# USB.net
KiCad netlist of a schematic drawn in Altium Designer
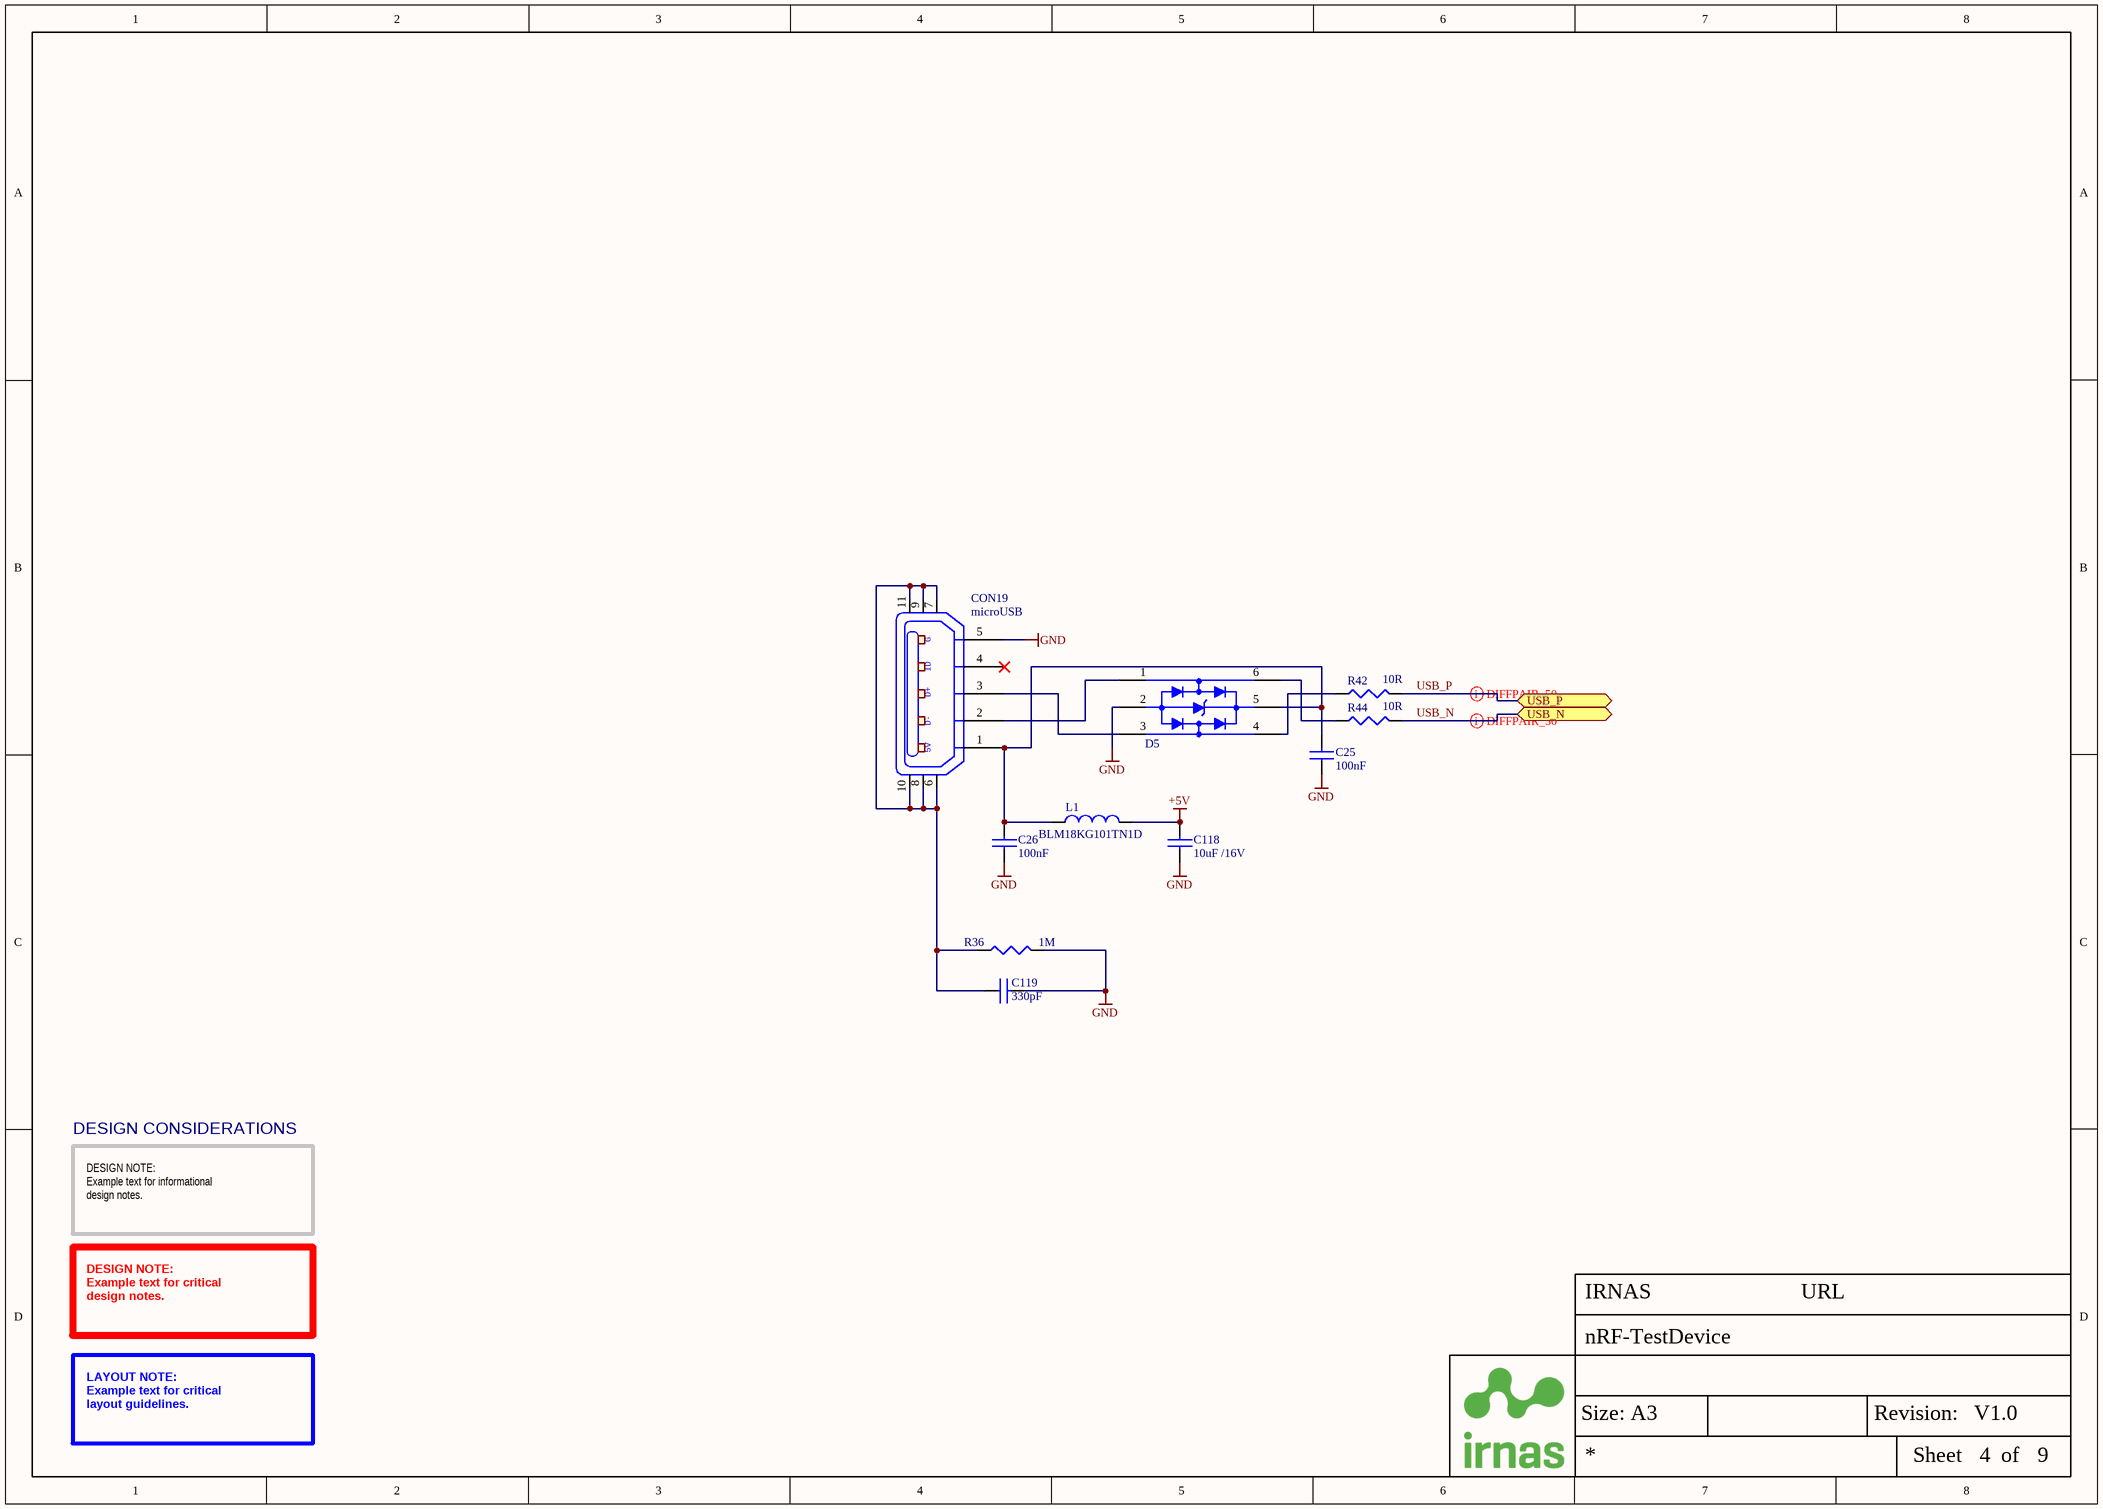
[diagram p0: USB.SchDoc]

(export (version "E")
  (design (tool "Eeschema 10.0.6"))
  (components
    (comp (ref "C25")
      (value "100nF")
      (footprint "CAP0402")
      (fields
        (field (name "MANUFACTURER") "Multicomp")
        (field (name "MANUFACTURER PART NUMBER") "MC0402X104J160CT")
        (field (name "TOLERANCE") "5%")
      )
      (libsource (lib "Passive") (part "C - 100nF/0402"))
    )
    (comp (ref "C26")
      (value "100nF")
      (footprint "CAP0402")
      (fields
        (field (name "MANUFACTURER") "Multicomp")
        (field (name "MANUFACTURER PART NUMBER") "MC0402X104J160CT")
        (field (name "TOLERANCE") "5%")
      )
      (libsource (lib "Passive") (part "C - 100nF/0402"))
    )
    (comp (ref "C118")
      (value "10uF /16V")
      (footprint "CAP0805")
      (description "TDK - CGA4J1X5R1C106K125AC - CAP, MLCC, X5R, 10UF, 16V, 0805")
      (fields
        (field (name "MANUFACTURER") "TDK")
        (field (name "MANUFACTURER PART NUMBER") "CGA4J1X5R1C106K125AC")
      )
      (libsource (lib "Passive") (part "C - 10uF /16V"))
    )
    (comp (ref "C119")
      (value "330pF")
      (footprint "CAP0603")
      (description "Cap Ceramic 330pF 50V C0G 5% SMD 0603 125C Paper T/R")
      (fields
        (field (name "MANUFACTURER") "Walsin Technologies")
        (field (name "MANUFACTURER PART NUMBER") "0603N331J500CT")
      )
      (libsource (lib "Passive") (part "C - 330pF"))
    )
    (comp (ref "CON19")
      (value "microUSB")
      (footprint "microUSB-CHINA")
      (libsource (lib "Connectors") (part "Micro USB CHINA 1"))
    )
    (comp (ref "D5")
      (value "USBLC6-2SC6")
      (footprint "SOT23-6")
      (description "ESD Protection Device, 17 V, SOT-23, 6 Pins, 6 V, 85 W, USBLC Series")
      (libsource (lib "Active") (part "D_ESD - USBLC6-2SC6"))
    )
    (comp (ref "L1")
      (value "BLM18KG101TN1D")
      (footprint "IND0603")
      (description "Ferrite Bead, 0603 [1608 Metric], 100 ohm, 3 A, BLM18K Series, 0.03 ohm, ± 25%")
      (libsource (lib "Passive") (part "L - BLM18KG101TN1D"))
    )
    (comp (ref "R36")
      (value "1M")
      (footprint "RES0603")
      (description "MULTICOMP - MC0063W060311M - RES, THICK FILM, 1M, 1%, 0.063W, 0603")
      (fields
        (field (name "MANUFACTURER") "MULTICOMP")
        (field (name "MANUFACTURER PART NUMBER") "MC0063W060311M")
      )
      (libsource (lib "Passive") (part "R - 1M"))
    )
    (comp (ref "R42")
      (value "10R")
      (footprint "RES0402")
      (description "SMD Chip Resistor, 0402 [1005 Metric], 10 ohm, CRCW e3 Series, 50 V, Thick Film, 63 mW")
      (fields
        (field (name "MANUFACTURER") "VISHAY")
        (field (name "MANUFACTURER PART NUMBER") "RCA060310R0FKEA")
      )
      (libsource (lib "Passive") (part "R - 10R/0402"))
    )
    (comp (ref "R44")
      (value "10R")
      (footprint "RES0402")
      (description "SMD Chip Resistor, 0402 [1005 Metric], 10 ohm, CRCW e3 Series, 50 V, Thick Film, 63 mW")
      (fields
        (field (name "MANUFACTURER") "VISHAY")
        (field (name "MANUFACTURER PART NUMBER") "RCA060310R0FKEA")
      )
      (libsource (lib "Passive") (part "R - 10R/0402"))
    )
  )
  (nets
    (net (code "1") (name "+5V") (class "Default")
      (node (ref "C118") (pin "2") (pinfunction "2_2") (pintype "passive"))
      (node (ref "L1") (pin "2") (pinfunction "2_2") (pintype "passive"))
    )
    (net (code "2") (name "/USB_N") (class "Default")
      (node (ref "R44") (pin "2") (pinfunction "2_2") (pintype "passive"))
    )
    (net (code "3") (name "/USB_P") (class "Default")
      (node (ref "R42") (pin "2") (pinfunction "2_2") (pintype "passive"))
    )
    (net (code "4") (name "GND") (class "Default")
      (node (ref "C118") (pin "1") (pinfunction "1_1") (pintype "passive"))
      (node (ref "C119") (pin "2") (pinfunction "2_2") (pintype "passive"))
      (node (ref "C25") (pin "1") (pinfunction "1_1") (pintype "passive"))
      (node (ref "C26") (pin "1") (pinfunction "1_1") (pintype "passive"))
      (node (ref "CON19") (pin "5") (pinfunction "P5_5") (pintype "passive"))
      (node (ref "D5") (pin "2") (pinfunction "2_2") (pintype "passive"))
      (node (ref "R36") (pin "2") (pinfunction "2_2") (pintype "passive"))
    )
    (net (code "5") (name "Net-(C119-Pad1)") (class "Default")
      (node (ref "C119") (pin "1") (pinfunction "1_1") (pintype "passive"))
      (node (ref "CON19") (pin "10") (pinfunction "10_10") (pintype "passive"))
      (node (ref "CON19") (pin "11") (pinfunction "11_11") (pintype "passive"))
      (node (ref "CON19") (pin "6") (pinfunction "6_6") (pintype "passive"))
      (node (ref "CON19") (pin "7") (pinfunction "7_7") (pintype "passive"))
      (node (ref "CON19") (pin "8") (pinfunction "8_8") (pintype "passive"))
      (node (ref "CON19") (pin "9") (pinfunction "9_9") (pintype "passive"))
      (node (ref "R36") (pin "1") (pinfunction "1_1") (pintype "passive"))
    )
    (net (code "6") (name "Net-(CON19-P1)") (class "Default")
      (node (ref "C25") (pin "2") (pinfunction "2_2") (pintype "passive"))
      (node (ref "C26") (pin "2") (pinfunction "2_2") (pintype "passive"))
      (node (ref "CON19") (pin "1") (pinfunction "P1_1") (pintype "passive"))
      (node (ref "D5") (pin "5") (pinfunction "5_5") (pintype "passive"))
      (node (ref "L1") (pin "1") (pinfunction "1_1") (pintype "passive"))
    )
    (net (code "7") (name "Net-(CON19-P2)") (class "Default")
      (node (ref "CON19") (pin "2") (pinfunction "P2_2") (pintype "passive"))
      (node (ref "D5") (pin "1") (pinfunction "1_1") (pintype "passive"))
    )
    (net (code "8") (name "Net-(CON19-P3)") (class "Default")
      (node (ref "CON19") (pin "3") (pinfunction "P3_3") (pintype "passive"))
      (node (ref "D5") (pin "3") (pinfunction "3_3") (pintype "passive"))
    )
    (net (code "9") (name "Net-(D5-Pad4)") (class "Default")
      (node (ref "D5") (pin "4") (pinfunction "4_4") (pintype "passive"))
      (node (ref "R42") (pin "1") (pinfunction "1_1") (pintype "passive"))
    )
    (net (code "10") (name "Net-(D5-Pad6)") (class "Default")
      (node (ref "D5") (pin "6") (pinfunction "6_6") (pintype "passive"))
      (node (ref "R44") (pin "1") (pinfunction "1_1") (pintype "passive"))
    )
    (net (code "11") (name "unconnected-(CON19-P4-Pad4)") (class "Default")
      (node (ref "CON19") (pin "4") (pinfunction "P4_4") (pintype "passive+no_connect"))
    )
  )
)
